# syspcb.net
KiCad netlist of a schematic drawn in Altium Designer
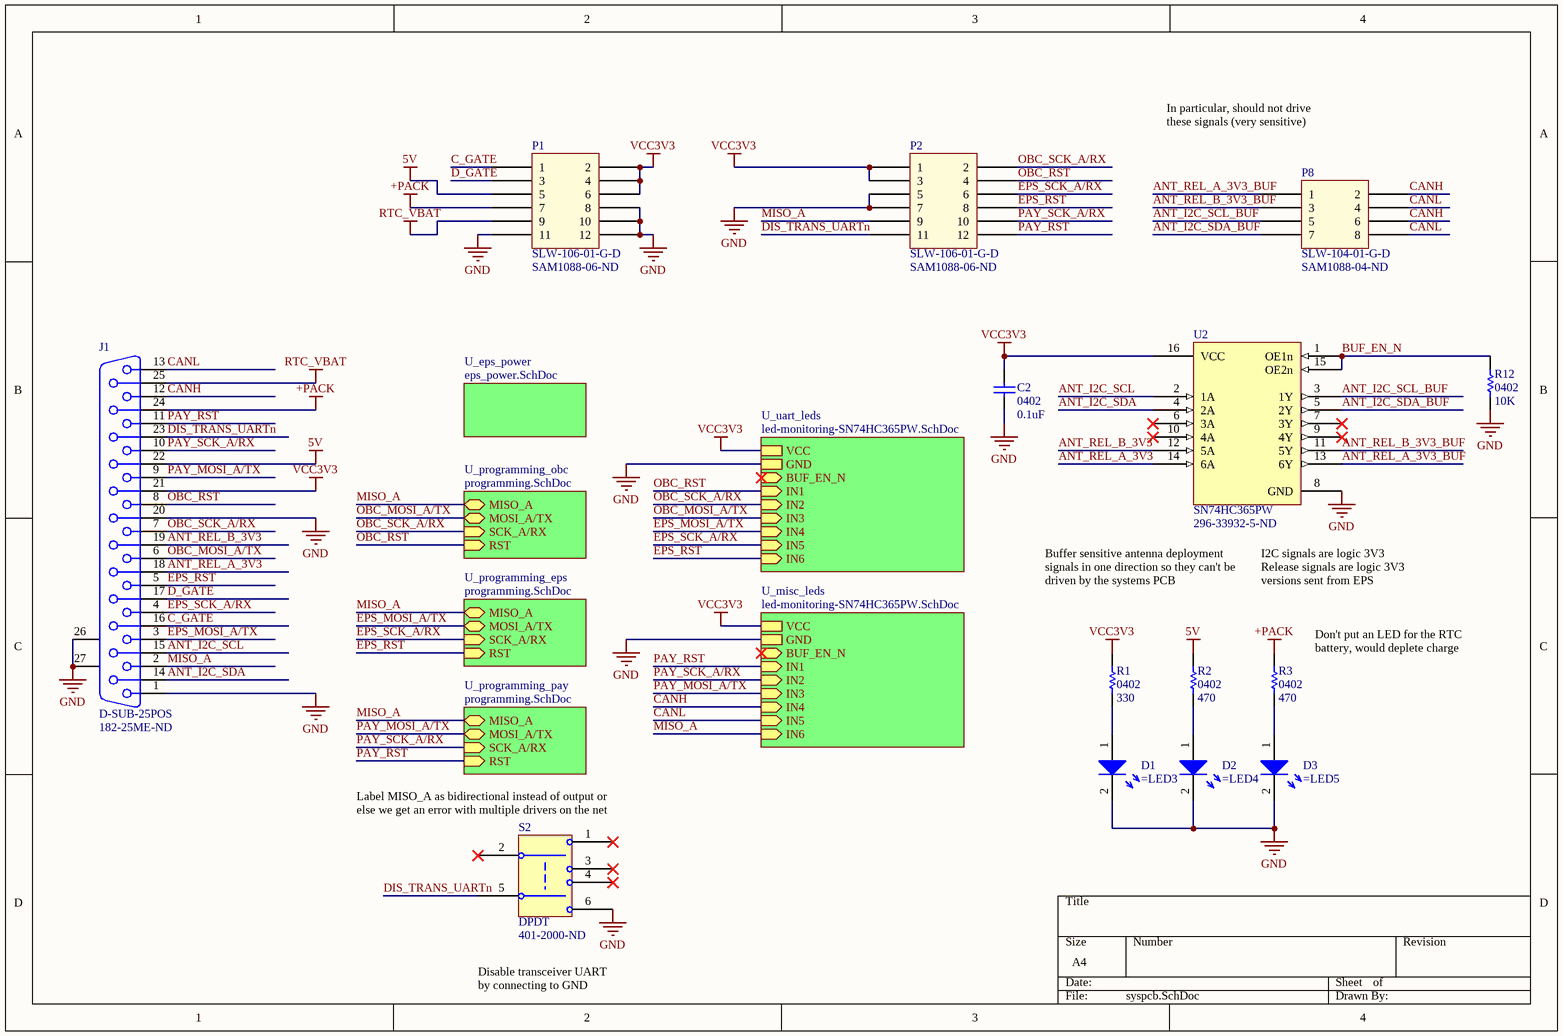
[diagram p0: syspcb.SchDoc]

(export (version "E")
  (design (tool "Eeschema 10.0.6"))
  (components
    (comp (ref "C2")
      (value "0402")
      (footprint "CAP0402R")
      (description "0402 capacitor")
      (fields
        (field (name "ALTIUM_VALUE") "0.1uF")
        (field (name "MANUFACTURER") "Taiyo Yuden")
        (field (name "MANUFACTURER PART NUMBER") "EMK105B7104KVHF")
      )
      (libsource (lib "heron-general") (part "CAP0402"))
    )
    (comp (ref "D1")
      (value "~")
      (footprint "LED0603")
      (description "Generic 0603 LED. Use ChipLED from Osram for generic ones.")
      (libsource (lib "heron-general") (part "LED0603"))
    )
    (comp (ref "D2")
      (value "~")
      (footprint "LED0603")
      (description "Generic 0603 LED. Use ChipLED from Osram for generic ones.")
      (libsource (lib "heron-general") (part "LED0603"))
    )
    (comp (ref "D3")
      (value "~")
      (footprint "LED0603")
      (description "Generic 0603 LED. Use ChipLED from Osram for generic ones.")
      (libsource (lib "heron-general") (part "LED0603"))
    )
    (comp (ref "J1")
      (value "D-SUB-25POS")
      (footprint "D-SUB-25POS")
      (description "CONN D-SUB PLUG 25POS R/A SOLDER")
      (fields (field (name "SUPPLIER PART NUMBER 1") "182-25ME-ND"))
      (libsource (lib "heron-general") (part "D-SUB-25POS"))
    )
    (comp (ref "P1")
      (value "SLW-106-01-G-D")
      (footprint "SLW-106-01-X-D")
      (description "CONN RCPT 12POS 0.1 GOLD PCB")
      (fields (field (name "SUPPLIER PART NUMBER 1") "SAM1088-06-ND"))
      (libsource (lib "heron-general") (part "SLW-106-01-G-D"))
    )
    (comp (ref "P2")
      (value "SLW-106-01-G-D")
      (footprint "SLW-106-01-X-D")
      (description "CONN RCPT 12POS 0.1 GOLD PCB")
      (fields (field (name "SUPPLIER PART NUMBER 1") "SAM1088-06-ND"))
      (libsource (lib "heron-general") (part "SLW-106-01-G-D"))
    )
    (comp (ref "P8")
      (value "SLW-104-01-G-D")
      (footprint "SLW-104-01-X-D")
      (description "CONN RCPT 8POS 0.1 GOLD PCB")
      (fields (field (name "SUPPLIER PART NUMBER 1") "SAM1088-04-ND"))
      (libsource (lib "heron-general") (part "SLW-104-01-G-D"))
    )
    (comp (ref "R1")
      (value "0402")
      (footprint "RES0402R")
      (description "0402 resistor")
      (fields (field (name "ALTIUM_VALUE") "330"))
      (libsource (lib "heron-general") (part "RES0402"))
    )
    (comp (ref "R2")
      (value "0402")
      (footprint "RES0402R")
      (description "0402 resistor")
      (fields (field (name "ALTIUM_VALUE") "470"))
      (libsource (lib "heron-general") (part "RES0402"))
    )
    (comp (ref "R3")
      (value "0402")
      (footprint "RES0402R")
      (description "0402 resistor")
      (fields (field (name "ALTIUM_VALUE") "470"))
      (libsource (lib "heron-general") (part "RES0402"))
    )
    (comp (ref "R12")
      (value "0402")
      (footprint "RES0402R")
      (description "0402 resistor")
      (fields
        (field (name "ALTIUM_VALUE") "10K")
        (field (name "MANUFACTURER") "Panasonic")
        (field (name "MANUFACTURER PART NUMBER") "ERJ-2RKF1002X")
      )
      (libsource (lib "heron-general") (part "RES0402"))
    )
    (comp (ref "S2")
      (value "DPDT")
      (footprint "JS202011AQN - Slide Switch")
      (description "DPDT Switch, customized for the pinout of the JS202011AQN switch.")
      (fields (field (name "SUPPLIER PART NUMBER 1") "401-2000-ND"))
      (libsource (lib "heron-general") (part "DPDT Switch"))
    )
    (comp (ref "U2")
      (value "SN74HC365PW")
      (footprint "SOP65P640X120-16N")
      (description "Hex non-inverting buffer with 3-state outputs")
      (fields (field (name "SUPPLIER PART NUMBER 1") "296-33932-5-ND"))
      (libsource (lib "heron-general") (part "SN74HC365PW"))
    )
  )
  (nets
    (net (code "1") (name "+PACK") (class "Default")
      (node (ref "J1") (pin "24") (pinfunction "24_24") (pintype "passive"))
      (node (ref "P1") (pin "7") (pinfunction "7_7") (pintype "passive"))
      (node (ref "R3") (pin "2") (pinfunction "2_2") (pintype "passive"))
    )
    (net (code "2") (name "/ANT_I2C_SCL") (class "Default")
      (node (ref "J1") (pin "15") (pinfunction "15_15") (pintype "passive"))
      (node (ref "U2") (pin "2") (pinfunction "1A_2") (pintype "input"))
    )
    (net (code "3") (name "/ANT_I2C_SCL_BUF") (class "Default")
      (node (ref "P8") (pin "5") (pinfunction "5_5") (pintype "passive"))
      (node (ref "U2") (pin "3") (pinfunction "1Y_3") (pintype "output"))
    )
    (net (code "4") (name "/ANT_I2C_SDA") (class "Default")
      (node (ref "J1") (pin "14") (pinfunction "14_14") (pintype "passive"))
      (node (ref "U2") (pin "4") (pinfunction "2A_4") (pintype "input"))
    )
    (net (code "5") (name "/ANT_I2C_SDA_BUF") (class "Default")
      (node (ref "P8") (pin "7") (pinfunction "7_7") (pintype "passive"))
      (node (ref "U2") (pin "5") (pinfunction "2Y_5") (pintype "output"))
    )
    (net (code "6") (name "/ANT_REL_A_3V3") (class "Default")
      (node (ref "J1") (pin "18") (pinfunction "18_18") (pintype "passive"))
      (node (ref "U2") (pin "14") (pinfunction "6A_14") (pintype "input"))
    )
    (net (code "7") (name "/ANT_REL_A_3V3_BUF") (class "Default")
      (node (ref "P8") (pin "1") (pinfunction "1_1") (pintype "passive"))
      (node (ref "U2") (pin "13") (pinfunction "6Y_13") (pintype "output"))
    )
    (net (code "8") (name "/ANT_REL_B_3V3") (class "Default")
      (node (ref "J1") (pin "19") (pinfunction "19_19") (pintype "passive"))
      (node (ref "U2") (pin "12") (pinfunction "5A_12") (pintype "input"))
    )
    (net (code "9") (name "/ANT_REL_B_3V3_BUF") (class "Default")
      (node (ref "P8") (pin "3") (pinfunction "3_3") (pintype "passive"))
      (node (ref "U2") (pin "11") (pinfunction "5Y_11") (pintype "output"))
    )
    (net (code "10") (name "/BUF_EN_N") (class "Default")
      (node (ref "R12") (pin "2") (pinfunction "2_2") (pintype "passive"))
      (node (ref "U2") (pin "1") (pinfunction "OE1n_1") (pintype "input"))
      (node (ref "U2") (pin "15") (pinfunction "OE2n_15") (pintype "input"))
    )
    (net (code "13") (name "/CANH") (class "Default")
      (node (ref "J1") (pin "12") (pinfunction "12_12") (pintype "passive"))
      (node (ref "P8") (pin "2") (pinfunction "2_2") (pintype "passive"))
      (node (ref "P8") (pin "6") (pinfunction "6_6") (pintype "passive"))
    )
    (net (code "14") (name "/CANL") (class "Default")
      (node (ref "J1") (pin "13") (pinfunction "13_13") (pintype "passive"))
      (node (ref "P8") (pin "4") (pinfunction "4_4") (pintype "passive"))
      (node (ref "P8") (pin "8") (pinfunction "8_8") (pintype "passive"))
    )
    (net (code "15") (name "/C_GATE") (class "Default")
      (node (ref "J1") (pin "16") (pinfunction "16_16") (pintype "passive"))
      (node (ref "P1") (pin "1") (pinfunction "1_1") (pintype "passive"))
    )
    (net (code "16") (name "/DIS_TRANS_UARTn") (class "Default")
      (node (ref "J1") (pin "23") (pinfunction "23_23") (pintype "passive"))
      (node (ref "P2") (pin "11") (pinfunction "11_11") (pintype "passive"))
      (node (ref "S2") (pin "5") (pinfunction "POLE2_5") (pintype "passive"))
    )
    (net (code "17") (name "/D_GATE") (class "Default")
      (node (ref "J1") (pin "17") (pinfunction "17_17") (pintype "passive"))
      (node (ref "P1") (pin "3") (pinfunction "3_3") (pintype "passive"))
    )
    (net (code "18") (name "/EPS_MOSI_A{slash}TX") (class "Default")
      (node (ref "J1") (pin "3") (pinfunction "3_3") (pintype "passive"))
    )
    (net (code "19") (name "/EPS_RST") (class "Default")
      (node (ref "J1") (pin "5") (pinfunction "5_5") (pintype "passive"))
      (node (ref "P2") (pin "8") (pinfunction "8_8") (pintype "passive"))
    )
    (net (code "20") (name "/EPS_SCK_A{slash}RX") (class "Default")
      (node (ref "J1") (pin "4") (pinfunction "4_4") (pintype "passive"))
      (node (ref "P2") (pin "6") (pinfunction "6_6") (pintype "passive"))
    )
    (net (code "21") (name "/MISO_A") (class "Default")
      (node (ref "J1") (pin "2") (pinfunction "2_2") (pintype "passive"))
      (node (ref "P2") (pin "9") (pinfunction "9_9") (pintype "passive"))
    )
    (net (code "22") (name "/OBC_MOSI_A{slash}TX") (class "Default")
      (node (ref "J1") (pin "6") (pinfunction "6_6") (pintype "passive"))
    )
    (net (code "23") (name "/OBC_RST") (class "Default")
      (node (ref "J1") (pin "8") (pinfunction "8_8") (pintype "passive"))
      (node (ref "P2") (pin "4") (pinfunction "4_4") (pintype "passive"))
    )
    (net (code "24") (name "/OBC_SCK_A{slash}RX") (class "Default")
      (node (ref "J1") (pin "7") (pinfunction "7_7") (pintype "passive"))
      (node (ref "P2") (pin "2") (pinfunction "2_2") (pintype "passive"))
    )
    (net (code "25") (name "/PAY_MOSI_A{slash}TX") (class "Default")
      (node (ref "J1") (pin "9") (pinfunction "9_9") (pintype "passive"))
    )
    (net (code "26") (name "/PAY_RST") (class "Default")
      (node (ref "J1") (pin "11") (pinfunction "11_11") (pintype "passive"))
      (node (ref "P2") (pin "12") (pinfunction "12_12") (pintype "passive"))
    )
    (net (code "27") (name "/PAY_SCK_A{slash}RX") (class "Default")
      (node (ref "J1") (pin "10") (pinfunction "10_10") (pintype "passive"))
      (node (ref "P2") (pin "10") (pinfunction "10_10") (pintype "passive"))
    )
    (net (code "28") (name "5V") (class "Default")
      (node (ref "J1") (pin "22") (pinfunction "22_22") (pintype "passive"))
      (node (ref "P1") (pin "5") (pinfunction "5_5") (pintype "passive"))
      (node (ref "R2") (pin "2") (pinfunction "2_2") (pintype "passive"))
    )
    (net (code "29") (name "GND") (class "Default")
      (node (ref "C2") (pin "1") (pinfunction "1_1") (pintype "passive"))
      (node (ref "D1") (pin "2") (pinfunction "2_2") (pintype "passive"))
      (node (ref "D2") (pin "2") (pinfunction "2_2") (pintype "passive"))
      (node (ref "D3") (pin "2") (pinfunction "2_2") (pintype "passive"))
      (node (ref "J1") (pin "1") (pinfunction "1_1") (pintype "passive"))
      (node (ref "J1") (pin "20") (pinfunction "20_20") (pintype "passive"))
      (node (ref "J1") (pin "26") (pinfunction "MH1_26") (pintype "passive"))
      (node (ref "J1") (pin "27") (pinfunction "MH2_27") (pintype "passive"))
      (node (ref "P1") (pin "10") (pinfunction "10_10") (pintype "passive"))
      (node (ref "P1") (pin "11") (pinfunction "11_11") (pintype "passive"))
      (node (ref "P1") (pin "12") (pinfunction "12_12") (pintype "passive"))
      (node (ref "P1") (pin "8") (pinfunction "8_8") (pintype "passive"))
      (node (ref "P2") (pin "5") (pinfunction "5_5") (pintype "passive"))
      (node (ref "P2") (pin "7") (pinfunction "7_7") (pintype "passive"))
      (node (ref "R12") (pin "1") (pinfunction "1_1") (pintype "passive"))
      (node (ref "S2") (pin "6") (pinfunction "POLE2B_6") (pintype "passive"))
      (node (ref "U2") (pin "8") (pinfunction "GND_8") (pintype "power_in"))
    )
    (net (code "30") (name "Net-(D1-Pad1)") (class "Default")
      (node (ref "D1") (pin "1") (pinfunction "1_1") (pintype "passive"))
      (node (ref "R1") (pin "1") (pinfunction "1_1") (pintype "passive"))
    )
    (net (code "31") (name "Net-(D2-Pad1)") (class "Default")
      (node (ref "D2") (pin "1") (pinfunction "1_1") (pintype "passive"))
      (node (ref "R2") (pin "1") (pinfunction "1_1") (pintype "passive"))
    )
    (net (code "32") (name "Net-(D3-Pad1)") (class "Default")
      (node (ref "D3") (pin "1") (pinfunction "1_1") (pintype "passive"))
      (node (ref "R3") (pin "1") (pinfunction "1_1") (pintype "passive"))
    )
    (net (code "33") (name "RTC_VBAT") (class "Default")
      (node (ref "J1") (pin "25") (pinfunction "25_25") (pintype "passive"))
      (node (ref "P1") (pin "9") (pinfunction "9_9") (pintype "passive"))
    )
    (net (code "34") (name "VCC3V3") (class "Default")
      (node (ref "C2") (pin "2") (pinfunction "2_2") (pintype "passive"))
      (node (ref "J1") (pin "21") (pinfunction "21_21") (pintype "passive"))
      (node (ref "P1") (pin "2") (pinfunction "2_2") (pintype "passive"))
      (node (ref "P1") (pin "4") (pinfunction "4_4") (pintype "passive"))
      (node (ref "P1") (pin "6") (pinfunction "6_6") (pintype "passive"))
      (node (ref "P2") (pin "1") (pinfunction "1_1") (pintype "passive"))
      (node (ref "P2") (pin "3") (pinfunction "3_3") (pintype "passive"))
      (node (ref "R1") (pin "2") (pinfunction "2_2") (pintype "passive"))
      (node (ref "U2") (pin "16") (pinfunction "VCC_16") (pintype "power_in"))
    )
    (net (code "35") (name "unconnected-(S2-POLE1-Pad2)") (class "Default")
      (node (ref "S2") (pin "2") (pinfunction "POLE1_2") (pintype "passive+no_connect"))
    )
    (net (code "36") (name "unconnected-(S2-POLE1A-Pad1)") (class "Default")
      (node (ref "S2") (pin "1") (pinfunction "POLE1A_1") (pintype "passive+no_connect"))
    )
    (net (code "37") (name "unconnected-(S2-POLE1B-Pad3)") (class "Default")
      (node (ref "S2") (pin "3") (pinfunction "POLE1B_3") (pintype "passive+no_connect"))
    )
    (net (code "38") (name "unconnected-(S2-POLE2A-Pad4)") (class "Default")
      (node (ref "S2") (pin "4") (pinfunction "POLE2A_4") (pintype "passive+no_connect"))
    )
    (net (code "39") (name "unconnected-(U2-3A-Pad6)") (class "Default")
      (node (ref "U2") (pin "6") (pinfunction "3A_6") (pintype "input+no_connect"))
    )
    (net (code "40") (name "unconnected-(U2-3Y-Pad7)") (class "Default")
      (node (ref "U2") (pin "7") (pinfunction "3Y_7") (pintype "output+no_connect"))
    )
    (net (code "41") (name "unconnected-(U2-4A-Pad10)") (class "Default")
      (node (ref "U2") (pin "10") (pinfunction "4A_10") (pintype "input+no_connect"))
    )
    (net (code "42") (name "unconnected-(U2-4Y-Pad9)") (class "Default")
      (node (ref "U2") (pin "9") (pinfunction "4Y_9") (pintype "output+no_connect"))
    )
  )
)
